# Inverter_S001A.net
KiCad netlist of a schematic drawn in EAGLE
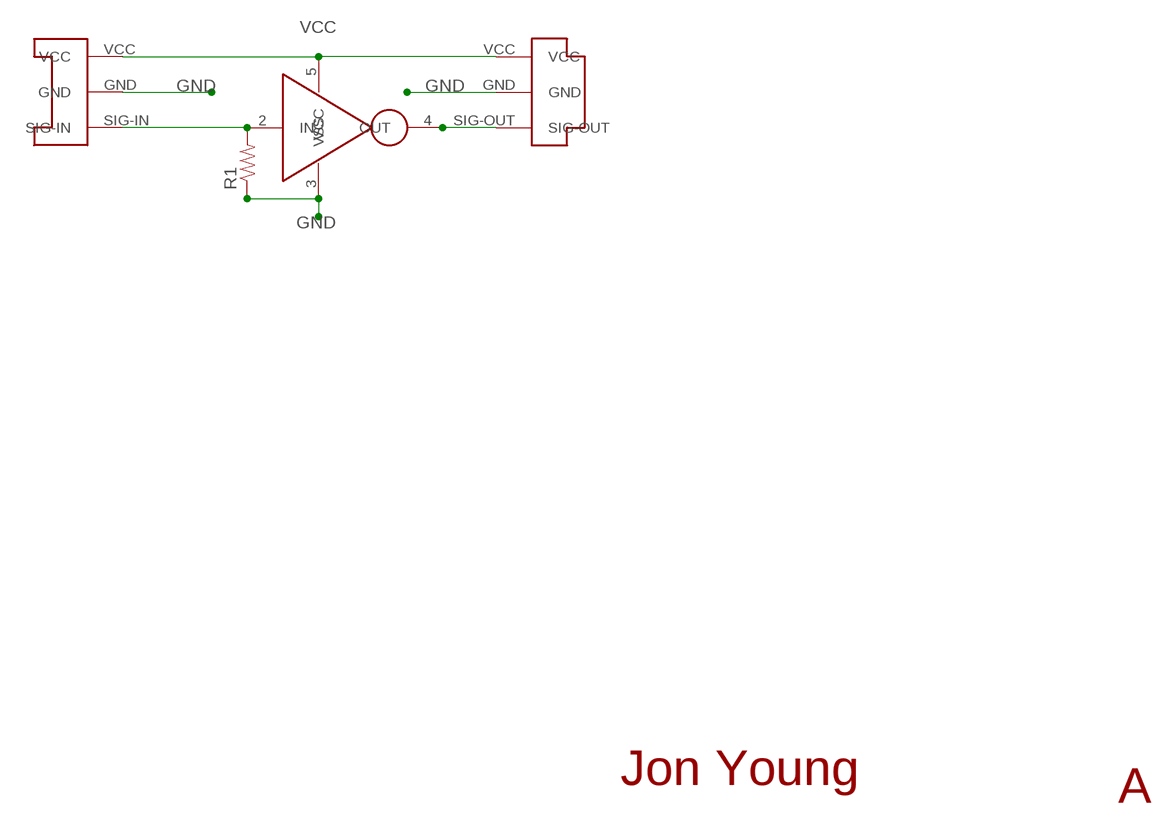
[diagram p0: schematic, sheet 1]

(export (version "E")
  (design (tool "Eeschema 10.0.6"))
  (components
    (comp (ref "R1")
      (value "RESISTOR0603")
      (footprint "eagle-import:0603-RES")
      (libsource (lib "eagle-import") (part "RESISTOR0603"))
    )
    (comp (ref "U$1")
      (value "CONN-PLUG-3POS-3MM")
      (footprint "eagle-import:PLUG-3POS-3MM-SMD")
      (libsource (lib "eagle-import") (part "CONN-PLUG-3POS-3MM"))
    )
    (comp (ref "U$2")
      (value "CONN-SOCKET-3POS-3MM")
      (footprint "eagle-import:SOCKET-3POS-3MM-SMD")
      (libsource (lib "eagle-import") (part "CONN-SOCKET-3POS-3MM"))
    )
    (comp (ref "U$3")
      (value "INV-NC7S145XCT-ND")
      (footprint "eagle-import:SC70")
      (libsource (lib "eagle-import") (part "INV-NC7S145XCT-ND"))
    )
  )
  (nets
    (net (code "1") (name "/GND") (class "Default")
      (node (ref "R1") (pin "1") (pinfunction "1_1") (pintype "passive"))
      (node (ref "U$1") (pin "GND") (pinfunction "GND_GND") (pintype "power_in"))
      (node (ref "U$2") (pin "GND") (pinfunction "GND_GND") (pintype "power_in"))
      (node (ref "U$3") (pin "3") (pinfunction "VSS_3") (pintype "power_in"))
    )
    (net (code "2") (name "/VCC") (class "Default")
      (node (ref "U$1") (pin "VCC") (pinfunction "VCC_VCC") (pintype "power_in"))
      (node (ref "U$2") (pin "VCC") (pinfunction "VCC_VCC") (pintype "power_in"))
      (node (ref "U$3") (pin "5") (pinfunction "VCC_5") (pintype "power_in"))
    )
    (net (code "3") (name "Net-(U$3-IN)") (class "Default")
      (node (ref "R1") (pin "2") (pinfunction "2_2") (pintype "passive"))
      (node (ref "U$2") (pin "SIG-IN") (pinfunction "SIG-IN_SIG-IN") (pintype "bidirectional"))
      (node (ref "U$3") (pin "2") (pinfunction "IN_2") (pintype "bidirectional"))
    )
    (net (code "4") (name "Net-(U$3-OUT)") (class "Default")
      (node (ref "U$1") (pin "SIG-OUT") (pinfunction "SIG-OUT_SIG-OUT") (pintype "bidirectional"))
      (node (ref "U$3") (pin "4") (pinfunction "OUT_4") (pintype "bidirectional"))
    )
  )
)
